# Voltage_Sensing.net
KiCad netlist of a schematic drawn in Altium Designer
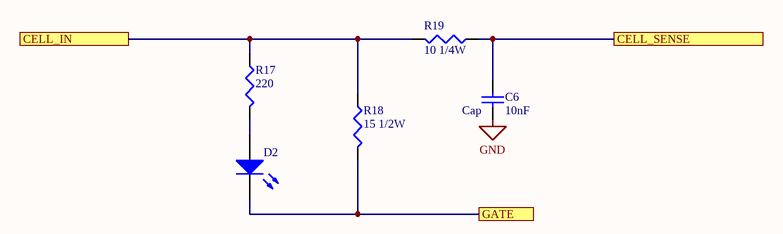
[diagram p0: Voltage Sensing.SchDoc]

(export (version "E")
  (design (tool "Eeschema 10.0.6"))
  (components
    (comp (ref "C6")
      (value "Cap")
      (footprint "0603 - Capacitor")
      (description "Capacitor")
      (fields (field (name "ALTIUM_VALUE") "10nF") (field (name "PUBLISHER") "Altium Limited"))
      (libsource (lib "Miscellaneous Devices") (part "Cap"))
    )
    (comp (ref "D2")
      (value "LED2")
      (footprint "DIOC1608X06N")
      (description "Typical RED, GREEN, YELLOW, AMBER GaAs LED")
      (fields (field (name "PUBLISHER") "Altium Limited"))
      (libsource (lib "Miscellaneous Devices") (part "LED2"))
    )
    (comp (ref "R17")
      (value "220")
      (footprint "0805 - Resistor")
      (description "Resistor")
      (fields (field (name "Comment") "Res3") (field (name "PUBLISHER") "Altium Limited"))
      (libsource (lib "Miscellaneous Devices") (part "Res3"))
    )
    (comp (ref "R18")
      (value "15 1/2W")
      (footprint "14-1210")
      (description "Resistor")
      (fields (field (name "Comment") "Res3") (field (name "PUBLISHER") "Altium Limited"))
      (libsource (lib "Miscellaneous Devices") (part "Res3"))
    )
    (comp (ref "R19")
      (value "10 1/4W")
      (footprint "0805 - Resistor")
      (description "Resistor")
      (fields (field (name "Comment") "Res3") (field (name "PUBLISHER") "Altium Limited"))
      (libsource (lib "Miscellaneous Devices") (part "Res3"))
    )
  )
  (nets
    (net (code "1") (name "/CELL_IN") (class "Default")
      (node (ref "R17") (pin "1") (pinfunction "1_1") (pintype "passive"))
      (node (ref "R18") (pin "1") (pinfunction "1_1") (pintype "passive"))
      (node (ref "R19") (pin "2") (pinfunction "2_2") (pintype "passive"))
    )
    (net (code "2") (name "/CELL_SENSE") (class "Default")
      (node (ref "C6") (pin "2") (pinfunction "2_2") (pintype "passive"))
      (node (ref "R19") (pin "1") (pinfunction "1_1") (pintype "passive"))
    )
    (net (code "3") (name "/GATE") (class "Default")
      (node (ref "D2") (pin "2") (pinfunction "K_2") (pintype "passive"))
      (node (ref "R18") (pin "2") (pinfunction "2_2") (pintype "passive"))
    )
    (net (code "4") (name "GND") (class "Default")
      (node (ref "C6") (pin "1") (pinfunction "1_1") (pintype "passive"))
    )
    (net (code "5") (name "Net-(D2-A)") (class "Default")
      (node (ref "D2") (pin "1") (pinfunction "A_1") (pintype "passive"))
      (node (ref "R17") (pin "2") (pinfunction "2_2") (pintype "passive"))
    )
  )
)
